# shield_confortimetro_bia_v2.net
KiCad netlist of a schematic drawn in EAGLE
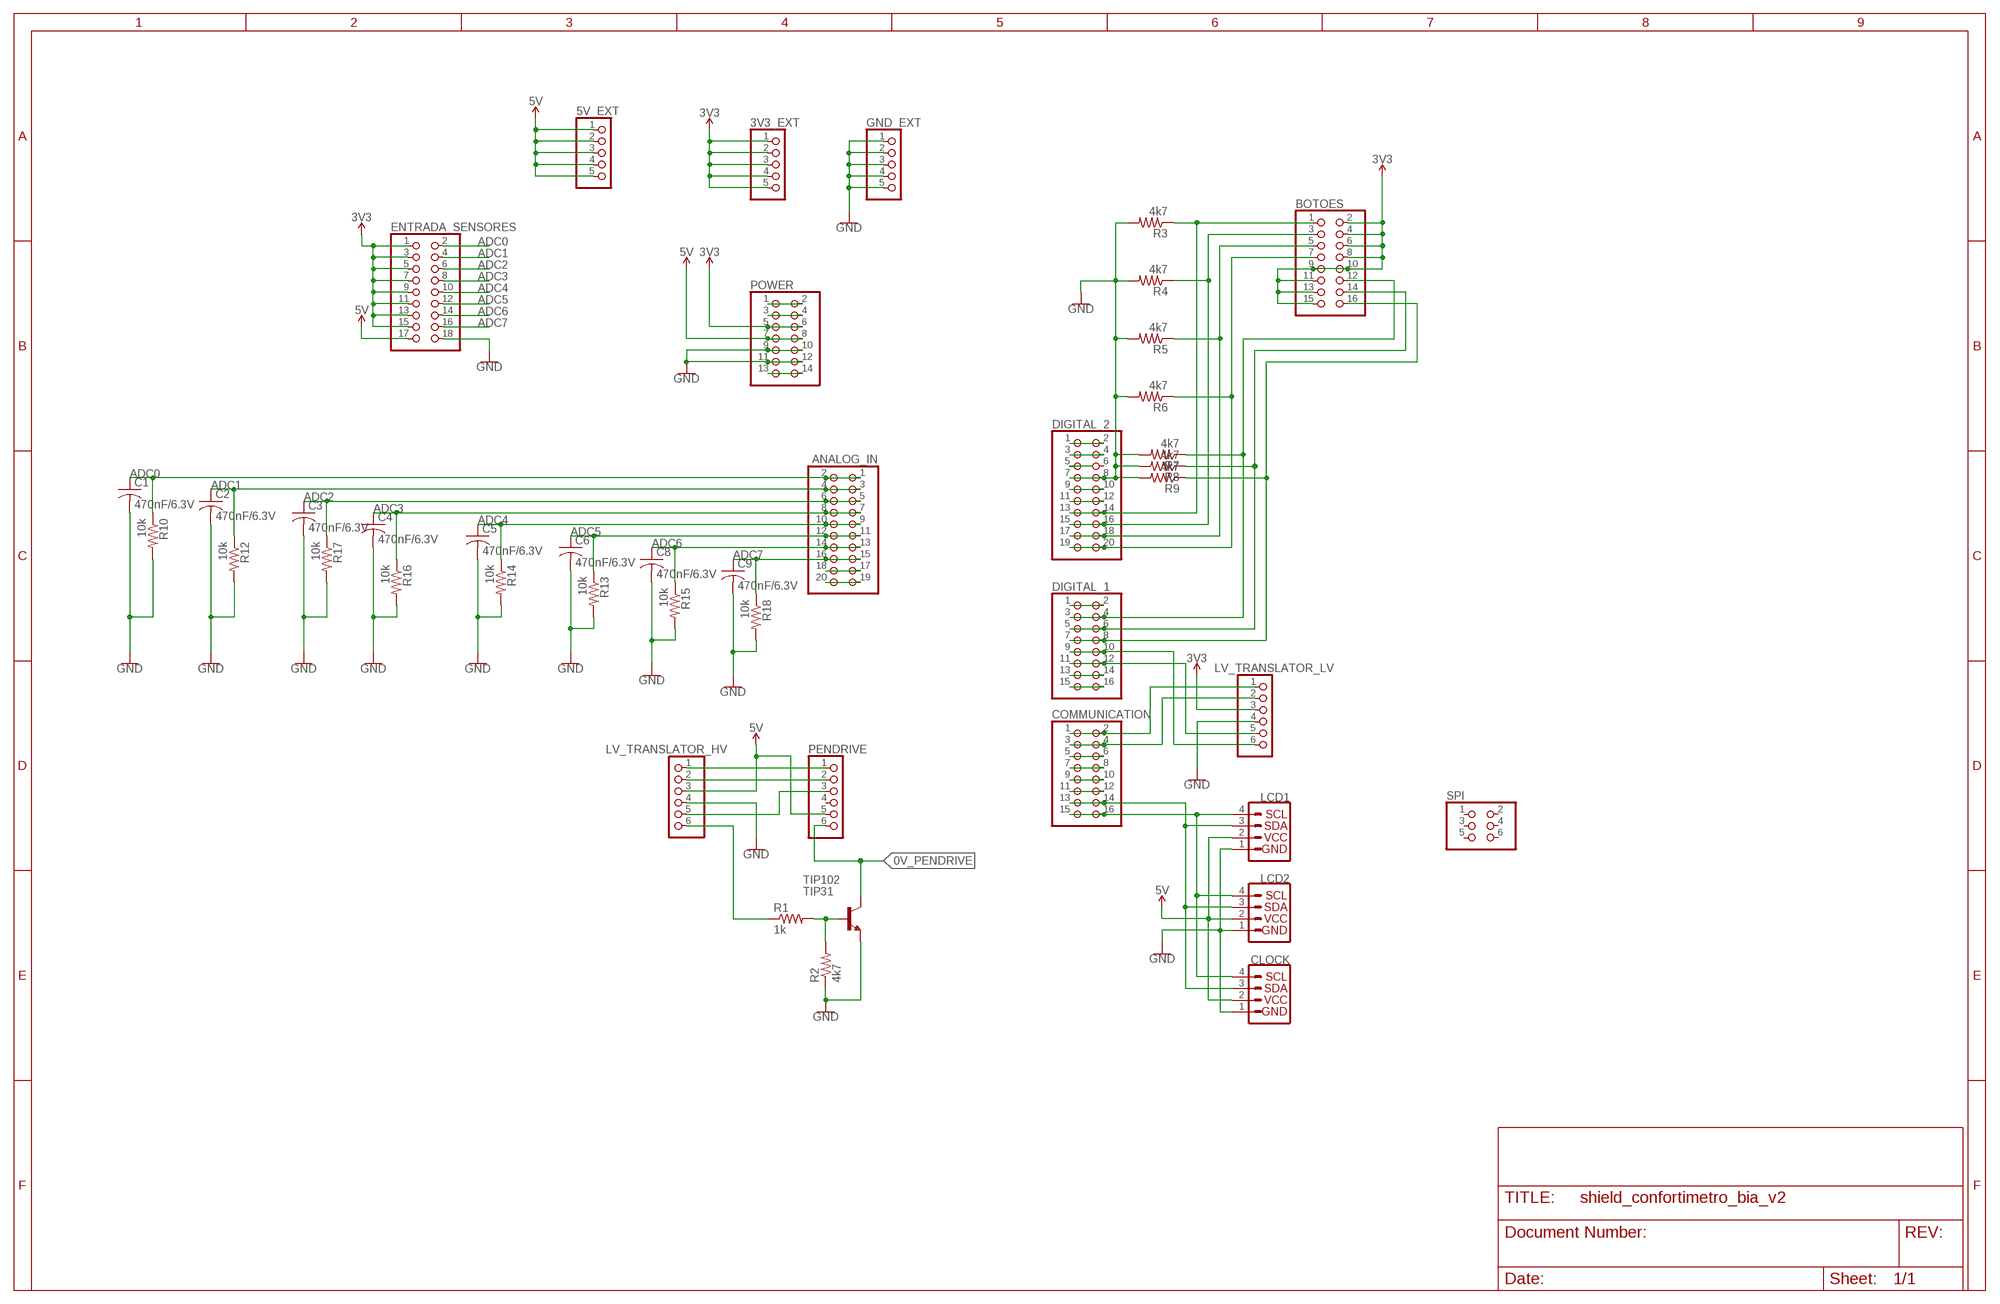
[diagram p0: schematic, sheet 1]

(export (version "E")
  (design (tool "Eeschema 10.0.6"))
  (components
    (comp (ref "3V3_EXT")
      (value "PINHD-1X5")
      (footprint "eagle-import:1X05")
      (libsource (lib "eagle-import") (part "PINHD-1X5"))
    )
    (comp (ref "5V_EXT")
      (value "PINHD-1X5")
      (footprint "eagle-import:1X05")
      (libsource (lib "eagle-import") (part "PINHD-1X5"))
    )
    (comp (ref "ANALOG_IN")
      (value "PINHD-2X10")
      (footprint "eagle-import:2X10")
      (libsource (lib "eagle-import") (part "PINHD-2X10"))
    )
    (comp (ref "BOTOES")
      (value "PINHD-2X8")
      (footprint "eagle-import:2X08")
      (libsource (lib "eagle-import") (part "PINHD-2X8"))
    )
    (comp (ref "C1")
      (value "470nF/6.3V")
      (footprint "eagle-import:C050-030X075")
      (libsource (lib "eagle-import") (part "C-US050-030X075"))
    )
    (comp (ref "C2")
      (value "470nF/6.3V")
      (footprint "eagle-import:C050-030X075")
      (libsource (lib "eagle-import") (part "C-US050-030X075"))
    )
    (comp (ref "C3")
      (value "470nF/6.3V")
      (footprint "eagle-import:C050-030X075")
      (libsource (lib "eagle-import") (part "C-US050-030X075"))
    )
    (comp (ref "C4")
      (value "470nF/6.3V")
      (footprint "eagle-import:C050-030X075")
      (libsource (lib "eagle-import") (part "C-US050-030X075"))
    )
    (comp (ref "C5")
      (value "470nF/6.3V")
      (footprint "eagle-import:C050-030X075")
      (libsource (lib "eagle-import") (part "C-US050-030X075"))
    )
    (comp (ref "C6")
      (value "470nF/6.3V")
      (footprint "eagle-import:C050-030X075")
      (libsource (lib "eagle-import") (part "C-US050-030X075"))
    )
    (comp (ref "C8")
      (value "470nF/6.3V")
      (footprint "eagle-import:C050-030X075")
      (libsource (lib "eagle-import") (part "C-US050-030X075"))
    )
    (comp (ref "C9")
      (value "470nF/6.3V")
      (footprint "eagle-import:C050-030X075")
      (libsource (lib "eagle-import") (part "C-US050-030X075"))
    )
    (comp (ref "CLOCK")
      (value "I2C_STANDARD")
      (footprint "eagle-import:1X04")
      (libsource (lib "eagle-import") (part "I2C_STANDARD"))
    )
    (comp (ref "COMMUNICATION")
      (value "PINHD-2X8")
      (footprint "eagle-import:2X08")
      (libsource (lib "eagle-import") (part "PINHD-2X8"))
    )
    (comp (ref "DIGITAL_1")
      (value "PINHD-2X8")
      (footprint "eagle-import:2X08")
      (libsource (lib "eagle-import") (part "PINHD-2X8"))
    )
    (comp (ref "DIGITAL_2")
      (value "PINHD-2X10")
      (footprint "eagle-import:2X10")
      (libsource (lib "eagle-import") (part "pinhead_PINHD-2X10"))
    )
    (comp (ref "ENTRADA_SENSORES")
      (value "PINHD-2X9")
      (footprint "eagle-import:2X09")
      (libsource (lib "eagle-import") (part "PINHD-2X9"))
    )
    (comp (ref "GND_EXT")
      (value "PINHD-1X5")
      (footprint "eagle-import:1X05")
      (libsource (lib "eagle-import") (part "PINHD-1X5"))
    )
    (comp (ref "LCD1")
      (value "I2C_STANDARD")
      (footprint "eagle-import:1X04")
      (libsource (lib "eagle-import") (part "I2C_STANDARD"))
    )
    (comp (ref "LCD2")
      (value "I2C_STANDARD")
      (footprint "eagle-import:1X04")
      (libsource (lib "eagle-import") (part "I2C_STANDARD"))
    )
    (comp (ref "LV_TRANSLATOR_HV")
      (value "PINHD-1X6")
      (footprint "eagle-import:1X06")
      (libsource (lib "eagle-import") (part "PINHD-1X6"))
    )
    (comp (ref "LV_TRANSLATOR_LV")
      (value "PINHD-1X6")
      (footprint "eagle-import:1X06")
      (libsource (lib "eagle-import") (part "PINHD-1X6"))
    )
    (comp (ref "PENDRIVE")
      (value "PINHD-1X6")
      (footprint "eagle-import:1X06")
      (libsource (lib "eagle-import") (part "PINHD-1X6"))
    )
    (comp (ref "POWER")
      (value "PINHD-2X7")
      (footprint "eagle-import:2X07")
      (libsource (lib "eagle-import") (part "PINHD-2X7"))
    )
    (comp (ref "R1")
      (value "1k")
      (footprint "eagle-import:0309_12")
      (libsource (lib "eagle-import") (part "R-US_0309/12"))
    )
    (comp (ref "R2")
      (value "4k7")
      (footprint "eagle-import:0309_12")
      (libsource (lib "eagle-import") (part "R-US_0309/12"))
    )
    (comp (ref "R3")
      (value "4k7")
      (footprint "eagle-import:0309_12")
      (libsource (lib "eagle-import") (part "R-US_0309/12"))
    )
    (comp (ref "R4")
      (value "4k7")
      (footprint "eagle-import:0309_12")
      (libsource (lib "eagle-import") (part "R-US_0309/12"))
    )
    (comp (ref "R5")
      (value "4k7")
      (footprint "eagle-import:0309_12")
      (libsource (lib "eagle-import") (part "R-US_0309/12"))
    )
    (comp (ref "R6")
      (value "4k7")
      (footprint "eagle-import:0309_12")
      (libsource (lib "eagle-import") (part "R-US_0309/12"))
    )
    (comp (ref "R7")
      (value "4k7")
      (footprint "eagle-import:0309_12")
      (libsource (lib "eagle-import") (part "R-US_0309/12"))
    )
    (comp (ref "R8")
      (value "4k7")
      (footprint "eagle-import:0309_12")
      (libsource (lib "eagle-import") (part "R-US_0309/12"))
    )
    (comp (ref "R9")
      (value "4k7")
      (footprint "eagle-import:0309_12")
      (libsource (lib "eagle-import") (part "R-US_0309/12"))
    )
    (comp (ref "R10")
      (value "10k")
      (footprint "eagle-import:0309_12")
      (libsource (lib "eagle-import") (part "R-US_0309/12"))
    )
    (comp (ref "R12")
      (value "10k")
      (footprint "eagle-import:0309_12")
      (libsource (lib "eagle-import") (part "R-US_0309/12"))
    )
    (comp (ref "R13")
      (value "10k")
      (footprint "eagle-import:0309_12")
      (libsource (lib "eagle-import") (part "R-US_0309/12"))
    )
    (comp (ref "R14")
      (value "10k")
      (footprint "eagle-import:0309_12")
      (libsource (lib "eagle-import") (part "R-US_0309/12"))
    )
    (comp (ref "R15")
      (value "10k")
      (footprint "eagle-import:0309_12")
      (libsource (lib "eagle-import") (part "R-US_0309/12"))
    )
    (comp (ref "R16")
      (value "10k")
      (footprint "eagle-import:0309_12")
      (libsource (lib "eagle-import") (part "R-US_0309/12"))
    )
    (comp (ref "R17")
      (value "10k")
      (footprint "eagle-import:0309_12")
      (libsource (lib "eagle-import") (part "R-US_0309/12"))
    )
    (comp (ref "R18")
      (value "10k")
      (footprint "eagle-import:0309_12")
      (libsource (lib "eagle-import") (part "R-US_0309/12"))
    )
    (comp (ref "SPI")
      (value "PINHD-2X3")
      (footprint "eagle-import:2X03")
      (libsource (lib "eagle-import") (part "PINHD-2X3"))
    )
    (comp (ref "TIP102")
      (value "TIP31")
      (footprint "eagle-import:TO220")
      (libsource (lib "eagle-import") (part "TIP31"))
    )
  )
  (nets
    (net (code "1") (name "/ADC0") (class "Default")
      (node (ref "ANALOG_IN") (pin "1") (pinfunction "1_1") (pintype "passive"))
      (node (ref "ANALOG_IN") (pin "2") (pinfunction "2_2") (pintype "passive"))
      (node (ref "C1") (pin "1") (pinfunction "1_1") (pintype "passive"))
      (node (ref "ENTRADA_SENSORES") (pin "2") (pinfunction "2_2") (pintype "passive"))
      (node (ref "R10") (pin "1") (pinfunction "1_1") (pintype "passive"))
    )
    (net (code "2") (name "/ADC1") (class "Default")
      (node (ref "ANALOG_IN") (pin "3") (pinfunction "3_3") (pintype "passive"))
      (node (ref "ANALOG_IN") (pin "4") (pinfunction "4_4") (pintype "passive"))
      (node (ref "C2") (pin "1") (pinfunction "1_1") (pintype "passive"))
      (node (ref "ENTRADA_SENSORES") (pin "4") (pinfunction "4_4") (pintype "passive"))
      (node (ref "R12") (pin "1") (pinfunction "1_1") (pintype "passive"))
    )
    (net (code "3") (name "/ADC2") (class "Default")
      (node (ref "ANALOG_IN") (pin "5") (pinfunction "5_5") (pintype "passive"))
      (node (ref "ANALOG_IN") (pin "6") (pinfunction "6_6") (pintype "passive"))
      (node (ref "C3") (pin "1") (pinfunction "1_1") (pintype "passive"))
      (node (ref "ENTRADA_SENSORES") (pin "6") (pinfunction "6_6") (pintype "passive"))
      (node (ref "R17") (pin "1") (pinfunction "1_1") (pintype "passive"))
    )
    (net (code "4") (name "/ADC3") (class "Default")
      (node (ref "ANALOG_IN") (pin "7") (pinfunction "7_7") (pintype "passive"))
      (node (ref "ANALOG_IN") (pin "8") (pinfunction "8_8") (pintype "passive"))
      (node (ref "C4") (pin "1") (pinfunction "1_1") (pintype "passive"))
      (node (ref "ENTRADA_SENSORES") (pin "8") (pinfunction "8_8") (pintype "passive"))
      (node (ref "R16") (pin "1") (pinfunction "1_1") (pintype "passive"))
    )
    (net (code "5") (name "/ADC4") (class "Default")
      (node (ref "ANALOG_IN") (pin "10") (pinfunction "10_10") (pintype "passive"))
      (node (ref "ANALOG_IN") (pin "9") (pinfunction "9_9") (pintype "passive"))
      (node (ref "C5") (pin "1") (pinfunction "1_1") (pintype "passive"))
      (node (ref "ENTRADA_SENSORES") (pin "10") (pinfunction "10_10") (pintype "passive"))
      (node (ref "R14") (pin "1") (pinfunction "1_1") (pintype "passive"))
    )
    (net (code "6") (name "/ADC5") (class "Default")
      (node (ref "ANALOG_IN") (pin "11") (pinfunction "11_11") (pintype "passive"))
      (node (ref "ANALOG_IN") (pin "12") (pinfunction "12_12") (pintype "passive"))
      (node (ref "C6") (pin "1") (pinfunction "1_1") (pintype "passive"))
      (node (ref "ENTRADA_SENSORES") (pin "12") (pinfunction "12_12") (pintype "passive"))
      (node (ref "R13") (pin "1") (pinfunction "1_1") (pintype "passive"))
    )
    (net (code "7") (name "/ADC6") (class "Default")
      (node (ref "ANALOG_IN") (pin "13") (pinfunction "13_13") (pintype "passive"))
      (node (ref "ANALOG_IN") (pin "14") (pinfunction "14_14") (pintype "passive"))
      (node (ref "C8") (pin "1") (pinfunction "1_1") (pintype "passive"))
      (node (ref "ENTRADA_SENSORES") (pin "14") (pinfunction "14_14") (pintype "passive"))
      (node (ref "R15") (pin "1") (pinfunction "1_1") (pintype "passive"))
    )
    (net (code "8") (name "/ADC7") (class "Default")
      (node (ref "ANALOG_IN") (pin "15") (pinfunction "15_15") (pintype "passive"))
      (node (ref "ANALOG_IN") (pin "16") (pinfunction "16_16") (pintype "passive"))
      (node (ref "C9") (pin "1") (pinfunction "1_1") (pintype "passive"))
      (node (ref "ENTRADA_SENSORES") (pin "16") (pinfunction "16_16") (pintype "passive"))
      (node (ref "R18") (pin "1") (pinfunction "1_1") (pintype "passive"))
    )
    (net (code "9") (name "0V_PENDRIVE") (class "Default")
      (node (ref "PENDRIVE") (pin "6") (pinfunction "6_6") (pintype "passive"))
      (node (ref "TIP102") (pin "2") (pinfunction "C_2") (pintype "passive"))
    )
    (net (code "10") (name "3V3") (class "Default")
      (node (ref "3V3_EXT") (pin "1") (pinfunction "1_1") (pintype "passive"))
      (node (ref "3V3_EXT") (pin "2") (pinfunction "2_2") (pintype "passive"))
      (node (ref "3V3_EXT") (pin "3") (pinfunction "3_3") (pintype "passive"))
      (node (ref "3V3_EXT") (pin "4") (pinfunction "4_4") (pintype "passive"))
      (node (ref "3V3_EXT") (pin "5") (pinfunction "5_5") (pintype "passive"))
      (node (ref "BOTOES") (pin "10") (pinfunction "10_10") (pintype "passive"))
      (node (ref "BOTOES") (pin "11") (pinfunction "11_11") (pintype "passive"))
      (node (ref "BOTOES") (pin "13") (pinfunction "13_13") (pintype "passive"))
      (node (ref "BOTOES") (pin "15") (pinfunction "15_15") (pintype "passive"))
      (node (ref "BOTOES") (pin "2") (pinfunction "2_2") (pintype "passive"))
      (node (ref "BOTOES") (pin "4") (pinfunction "4_4") (pintype "passive"))
      (node (ref "BOTOES") (pin "6") (pinfunction "6_6") (pintype "passive"))
      (node (ref "BOTOES") (pin "8") (pinfunction "8_8") (pintype "passive"))
      (node (ref "BOTOES") (pin "9") (pinfunction "9_9") (pintype "passive"))
      (node (ref "ENTRADA_SENSORES") (pin "1") (pinfunction "1_1") (pintype "passive"))
      (node (ref "ENTRADA_SENSORES") (pin "11") (pinfunction "11_11") (pintype "passive"))
      (node (ref "ENTRADA_SENSORES") (pin "13") (pinfunction "13_13") (pintype "passive"))
      (node (ref "ENTRADA_SENSORES") (pin "15") (pinfunction "15_15") (pintype "passive"))
      (node (ref "ENTRADA_SENSORES") (pin "3") (pinfunction "3_3") (pintype "passive"))
      (node (ref "ENTRADA_SENSORES") (pin "5") (pinfunction "5_5") (pintype "passive"))
      (node (ref "ENTRADA_SENSORES") (pin "7") (pinfunction "7_7") (pintype "passive"))
      (node (ref "ENTRADA_SENSORES") (pin "9") (pinfunction "9_9") (pintype "passive"))
      (node (ref "LV_TRANSLATOR_LV") (pin "3") (pinfunction "3_3") (pintype "passive"))
      (node (ref "POWER") (pin "5") (pinfunction "5_5") (pintype "passive"))
      (node (ref "POWER") (pin "6") (pinfunction "6_6") (pintype "passive"))
    )
    (net (code "11") (name "5V") (class "Default")
      (node (ref "5V_EXT") (pin "1") (pinfunction "1_1") (pintype "passive"))
      (node (ref "5V_EXT") (pin "2") (pinfunction "2_2") (pintype "passive"))
      (node (ref "5V_EXT") (pin "3") (pinfunction "3_3") (pintype "passive"))
      (node (ref "5V_EXT") (pin "4") (pinfunction "4_4") (pintype "passive"))
      (node (ref "5V_EXT") (pin "5") (pinfunction "5_5") (pintype "passive"))
      (node (ref "CLOCK") (pin "2") (pinfunction "2_2") (pintype "power_in"))
      (node (ref "ENTRADA_SENSORES") (pin "17") (pinfunction "17_17") (pintype "passive"))
      (node (ref "LCD1") (pin "2") (pinfunction "2_2") (pintype "power_in"))
      (node (ref "LCD2") (pin "2") (pinfunction "2_2") (pintype "power_in"))
      (node (ref "LV_TRANSLATOR_HV") (pin "3") (pinfunction "3_3") (pintype "passive"))
      (node (ref "PENDRIVE") (pin "5") (pinfunction "5_5") (pintype "passive"))
      (node (ref "POWER") (pin "7") (pinfunction "7_7") (pintype "passive"))
      (node (ref "POWER") (pin "8") (pinfunction "8_8") (pintype "passive"))
    )
    (net (code "12") (name "GND") (class "Default")
      (node (ref "C1") (pin "2") (pinfunction "2_2") (pintype "passive"))
      (node (ref "C2") (pin "2") (pinfunction "2_2") (pintype "passive"))
      (node (ref "C3") (pin "2") (pinfunction "2_2") (pintype "passive"))
      (node (ref "C4") (pin "2") (pinfunction "2_2") (pintype "passive"))
      (node (ref "C5") (pin "2") (pinfunction "2_2") (pintype "passive"))
      (node (ref "C6") (pin "2") (pinfunction "2_2") (pintype "passive"))
      (node (ref "C8") (pin "2") (pinfunction "2_2") (pintype "passive"))
      (node (ref "C9") (pin "2") (pinfunction "2_2") (pintype "passive"))
      (node (ref "CLOCK") (pin "1") (pinfunction "1_1") (pintype "power_in"))
      (node (ref "DIGITAL_2") (pin "7") (pinfunction "7_7") (pintype "passive"))
      (node (ref "DIGITAL_2") (pin "8") (pinfunction "8_8") (pintype "passive"))
      (node (ref "ENTRADA_SENSORES") (pin "18") (pinfunction "18_18") (pintype "passive"))
      (node (ref "GND_EXT") (pin "1") (pinfunction "1_1") (pintype "passive"))
      (node (ref "GND_EXT") (pin "2") (pinfunction "2_2") (pintype "passive"))
      (node (ref "GND_EXT") (pin "3") (pinfunction "3_3") (pintype "passive"))
      (node (ref "GND_EXT") (pin "4") (pinfunction "4_4") (pintype "passive"))
      (node (ref "GND_EXT") (pin "5") (pinfunction "5_5") (pintype "passive"))
      (node (ref "LCD1") (pin "1") (pinfunction "1_1") (pintype "power_in"))
      (node (ref "LCD2") (pin "1") (pinfunction "1_1") (pintype "power_in"))
      (node (ref "LV_TRANSLATOR_HV") (pin "4") (pinfunction "4_4") (pintype "passive"))
      (node (ref "LV_TRANSLATOR_LV") (pin "4") (pinfunction "4_4") (pintype "passive"))
      (node (ref "POWER") (pin "10") (pinfunction "10_10") (pintype "passive"))
      (node (ref "POWER") (pin "11") (pinfunction "11_11") (pintype "passive"))
      (node (ref "POWER") (pin "12") (pinfunction "12_12") (pintype "passive"))
      (node (ref "POWER") (pin "9") (pinfunction "9_9") (pintype "passive"))
      (node (ref "R10") (pin "2") (pinfunction "2_2") (pintype "passive"))
      (node (ref "R12") (pin "2") (pinfunction "2_2") (pintype "passive"))
      (node (ref "R13") (pin "2") (pinfunction "2_2") (pintype "passive"))
      (node (ref "R14") (pin "2") (pinfunction "2_2") (pintype "passive"))
      (node (ref "R15") (pin "2") (pinfunction "2_2") (pintype "passive"))
      (node (ref "R16") (pin "2") (pinfunction "2_2") (pintype "passive"))
      (node (ref "R17") (pin "2") (pinfunction "2_2") (pintype "passive"))
      (node (ref "R18") (pin "2") (pinfunction "2_2") (pintype "passive"))
      (node (ref "R2") (pin "1") (pinfunction "1_1") (pintype "passive"))
      (node (ref "R3") (pin "2") (pinfunction "2_2") (pintype "passive"))
      (node (ref "R4") (pin "2") (pinfunction "2_2") (pintype "passive"))
      (node (ref "R5") (pin "2") (pinfunction "2_2") (pintype "passive"))
      (node (ref "R6") (pin "2") (pinfunction "2_2") (pintype "passive"))
      (node (ref "R7") (pin "2") (pinfunction "2_2") (pintype "passive"))
      (node (ref "R8") (pin "2") (pinfunction "2_2") (pintype "passive"))
      (node (ref "R9") (pin "2") (pinfunction "2_2") (pintype "passive"))
      (node (ref "TIP102") (pin "3") (pinfunction "E_3") (pintype "passive"))
    )
    (net (code "13") (name "Net-(ANALOG_IN-Pad17)") (class "Default")
      (node (ref "ANALOG_IN") (pin "17") (pinfunction "17_17") (pintype "passive"))
      (node (ref "ANALOG_IN") (pin "18") (pinfunction "18_18") (pintype "passive"))
    )
    (net (code "14") (name "Net-(ANALOG_IN-Pad19)") (class "Default")
      (node (ref "ANALOG_IN") (pin "19") (pinfunction "19_19") (pintype "passive"))
      (node (ref "ANALOG_IN") (pin "20") (pinfunction "20_20") (pintype "passive"))
    )
    (net (code "15") (name "Net-(BOTOES-Pad1)") (class "Default")
      (node (ref "BOTOES") (pin "1") (pinfunction "1_1") (pintype "passive"))
      (node (ref "DIGITAL_2") (pin "13") (pinfunction "13_13") (pintype "passive"))
      (node (ref "DIGITAL_2") (pin "14") (pinfunction "14_14") (pintype "passive"))
      (node (ref "R3") (pin "1") (pinfunction "1_1") (pintype "passive"))
    )
    (net (code "16") (name "Net-(BOTOES-Pad3)") (class "Default")
      (node (ref "BOTOES") (pin "3") (pinfunction "3_3") (pintype "passive"))
      (node (ref "DIGITAL_2") (pin "15") (pinfunction "15_15") (pintype "passive"))
      (node (ref "DIGITAL_2") (pin "16") (pinfunction "16_16") (pintype "passive"))
      (node (ref "R4") (pin "1") (pinfunction "1_1") (pintype "passive"))
    )
    (net (code "17") (name "Net-(BOTOES-Pad5)") (class "Default")
      (node (ref "BOTOES") (pin "5") (pinfunction "5_5") (pintype "passive"))
      (node (ref "DIGITAL_2") (pin "17") (pinfunction "17_17") (pintype "passive"))
      (node (ref "DIGITAL_2") (pin "18") (pinfunction "18_18") (pintype "passive"))
      (node (ref "R5") (pin "1") (pinfunction "1_1") (pintype "passive"))
    )
    (net (code "18") (name "Net-(BOTOES-Pad7)") (class "Default")
      (node (ref "BOTOES") (pin "7") (pinfunction "7_7") (pintype "passive"))
      (node (ref "DIGITAL_2") (pin "19") (pinfunction "19_19") (pintype "passive"))
      (node (ref "DIGITAL_2") (pin "20") (pinfunction "20_20") (pintype "passive"))
      (node (ref "R6") (pin "1") (pinfunction "1_1") (pintype "passive"))
    )
    (net (code "19") (name "Net-(BOTOES-Pad12)") (class "Default")
      (node (ref "BOTOES") (pin "12") (pinfunction "12_12") (pintype "passive"))
      (node (ref "DIGITAL_1") (pin "3") (pinfunction "3_3") (pintype "passive"))
      (node (ref "DIGITAL_1") (pin "4") (pinfunction "4_4") (pintype "passive"))
      (node (ref "R7") (pin "1") (pinfunction "1_1") (pintype "passive"))
    )
    (net (code "20") (name "Net-(BOTOES-Pad14)") (class "Default")
      (node (ref "BOTOES") (pin "14") (pinfunction "14_14") (pintype "passive"))
      (node (ref "DIGITAL_1") (pin "5") (pinfunction "5_5") (pintype "passive"))
      (node (ref "DIGITAL_1") (pin "6") (pinfunction "6_6") (pintype "passive"))
      (node (ref "R8") (pin "1") (pinfunction "1_1") (pintype "passive"))
    )
    (net (code "21") (name "Net-(BOTOES-Pad16)") (class "Default")
      (node (ref "BOTOES") (pin "16") (pinfunction "16_16") (pintype "passive"))
      (node (ref "DIGITAL_1") (pin "7") (pinfunction "7_7") (pintype "passive"))
      (node (ref "DIGITAL_1") (pin "8") (pinfunction "8_8") (pintype "passive"))
      (node (ref "R9") (pin "1") (pinfunction "1_1") (pintype "passive"))
    )
    (net (code "22") (name "Net-(CLOCK-Pad3)") (class "Default")
      (node (ref "CLOCK") (pin "3") (pinfunction "3_3") (pintype "passive"))
      (node (ref "COMMUNICATION") (pin "13") (pinfunction "13_13") (pintype "passive"))
      (node (ref "COMMUNICATION") (pin "14") (pinfunction "14_14") (pintype "passive"))
      (node (ref "LCD1") (pin "3") (pinfunction "3_3") (pintype "passive"))
      (node (ref "LCD2") (pin "3") (pinfunction "3_3") (pintype "passive"))
    )
    (net (code "23") (name "Net-(CLOCK-Pad4)") (class "Default")
      (node (ref "CLOCK") (pin "4") (pinfunction "4_4") (pintype "passive"))
      (node (ref "COMMUNICATION") (pin "15") (pinfunction "15_15") (pintype "passive"))
      (node (ref "COMMUNICATION") (pin "16") (pinfunction "16_16") (pintype "passive"))
      (node (ref "LCD1") (pin "4") (pinfunction "4_4") (pintype "passive"))
      (node (ref "LCD2") (pin "4") (pinfunction "4_4") (pintype "passive"))
    )
    (net (code "24") (name "Net-(COMMUNICATION-Pad1)") (class "Default")
      (node (ref "COMMUNICATION") (pin "1") (pinfunction "1_1") (pintype "passive"))
      (node (ref "COMMUNICATION") (pin "2") (pinfunction "2_2") (pintype "passive"))
      (node (ref "LV_TRANSLATOR_LV") (pin "1") (pinfunction "1_1") (pintype "passive"))
    )
    (net (code "25") (name "Net-(COMMUNICATION-Pad3)") (class "Default")
      (node (ref "COMMUNICATION") (pin "3") (pinfunction "3_3") (pintype "passive"))
      (node (ref "COMMUNICATION") (pin "4") (pinfunction "4_4") (pintype "passive"))
      (node (ref "LV_TRANSLATOR_LV") (pin "2") (pinfunction "2_2") (pintype "passive"))
    )
    (net (code "26") (name "Net-(COMMUNICATION-Pad5)") (class "Default")
      (node (ref "COMMUNICATION") (pin "5") (pinfunction "5_5") (pintype "passive"))
      (node (ref "COMMUNICATION") (pin "6") (pinfunction "6_6") (pintype "passive"))
    )
    (net (code "27") (name "Net-(COMMUNICATION-Pad7)") (class "Default")
      (node (ref "COMMUNICATION") (pin "7") (pinfunction "7_7") (pintype "passive"))
      (node (ref "COMMUNICATION") (pin "8") (pinfunction "8_8") (pintype "passive"))
    )
    (net (code "28") (name "Net-(COMMUNICATION-Pad10)") (class "Default")
      (node (ref "COMMUNICATION") (pin "10") (pinfunction "10_10") (pintype "passive"))
      (node (ref "COMMUNICATION") (pin "9") (pinfunction "9_9") (pintype "passive"))
    )
    (net (code "29") (name "Net-(COMMUNICATION-Pad11)") (class "Default")
      (node (ref "COMMUNICATION") (pin "11") (pinfunction "11_11") (pintype "passive"))
      (node (ref "COMMUNICATION") (pin "12") (pinfunction "12_12") (pintype "passive"))
    )
    (net (code "30") (name "Net-(DIGITAL_1-Pad1)") (class "Default")
      (node (ref "DIGITAL_1") (pin "1") (pinfunction "1_1") (pintype "passive"))
      (node (ref "DIGITAL_1") (pin "2") (pinfunction "2_2") (pintype "passive"))
    )
    (net (code "31") (name "Net-(DIGITAL_1-Pad10)") (class "Default")
      (node (ref "DIGITAL_1") (pin "10") (pinfunction "10_10") (pintype "passive"))
      (node (ref "DIGITAL_1") (pin "9") (pinfunction "9_9") (pintype "passive"))
      (node (ref "LV_TRANSLATOR_LV") (pin "6") (pinfunction "6_6") (pintype "passive"))
    )
    (net (code "32") (name "Net-(DIGITAL_1-Pad11)") (class "Default")
      (node (ref "DIGITAL_1") (pin "11") (pinfunction "11_11") (pintype "passive"))
      (node (ref "DIGITAL_1") (pin "12") (pinfunction "12_12") (pintype "passive"))
      (node (ref "LV_TRANSLATOR_LV") (pin "5") (pinfunction "5_5") (pintype "passive"))
    )
    (net (code "33") (name "Net-(DIGITAL_1-Pad13)") (class "Default")
      (node (ref "DIGITAL_1") (pin "13") (pinfunction "13_13") (pintype "passive"))
      (node (ref "DIGITAL_1") (pin "14") (pinfunction "14_14") (pintype "passive"))
    )
    (net (code "34") (name "Net-(DIGITAL_1-Pad15)") (class "Default")
      (node (ref "DIGITAL_1") (pin "15") (pinfunction "15_15") (pintype "passive"))
      (node (ref "DIGITAL_1") (pin "16") (pinfunction "16_16") (pintype "passive"))
    )
    (net (code "35") (name "Net-(DIGITAL_2-Pad1)") (class "Default")
      (node (ref "DIGITAL_2") (pin "1") (pinfunction "1_1") (pintype "passive"))
      (node (ref "DIGITAL_2") (pin "2") (pinfunction "2_2") (pintype "passive"))
    )
    (net (code "36") (name "Net-(DIGITAL_2-Pad3)") (class "Default")
      (node (ref "DIGITAL_2") (pin "3") (pinfunction "3_3") (pintype "passive"))
      (node (ref "DIGITAL_2") (pin "4") (pinfunction "4_4") (pintype "passive"))
    )
    (net (code "37") (name "Net-(DIGITAL_2-Pad10)") (class "Default")
      (node (ref "DIGITAL_2") (pin "10") (pinfunction "10_10") (pintype "passive"))
      (node (ref "DIGITAL_2") (pin "9") (pinfunction "9_9") (pintype "passive"))
    )
    (net (code "38") (name "Net-(DIGITAL_2-Pad11)") (class "Default")
      (node (ref "DIGITAL_2") (pin "11") (pinfunction "11_11") (pintype "passive"))
      (node (ref "DIGITAL_2") (pin "12") (pinfunction "12_12") (pintype "passive"))
    )
    (net (code "39") (name "Net-(LV_TRANSLATOR_HV-Pad1)") (class "Default")
      (node (ref "LV_TRANSLATOR_HV") (pin "1") (pinfunction "1_1") (pintype "passive"))
      (node (ref "PENDRIVE") (pin "1") (pinfunction "1_1") (pintype "passive"))
    )
    (net (code "40") (name "Net-(LV_TRANSLATOR_HV-Pad2)") (class "Default")
      (node (ref "LV_TRANSLATOR_HV") (pin "2") (pinfunction "2_2") (pintype "passive"))
      (node (ref "PENDRIVE") (pin "2") (pinfunction "2_2") (pintype "passive"))
    )
    (net (code "41") (name "Net-(LV_TRANSLATOR_HV-Pad5)") (class "Default")
      (node (ref "LV_TRANSLATOR_HV") (pin "5") (pinfunction "5_5") (pintype "passive"))
      (node (ref "PENDRIVE") (pin "3") (pinfunction "3_3") (pintype "passive"))
    )
    (net (code "42") (name "Net-(LV_TRANSLATOR_HV-Pad6)") (class "Default")
      (node (ref "LV_TRANSLATOR_HV") (pin "6") (pinfunction "6_6") (pintype "passive"))
      (node (ref "R1") (pin "1") (pinfunction "1_1") (pintype "passive"))
    )
    (net (code "43") (name "Net-(POWER-Pad1)") (class "Default")
      (node (ref "POWER") (pin "1") (pinfunction "1_1") (pintype "passive"))
      (node (ref "POWER") (pin "2") (pinfunction "2_2") (pintype "passive"))
    )
    (net (code "44") (name "Net-(POWER-Pad3)") (class "Default")
      (node (ref "POWER") (pin "3") (pinfunction "3_3") (pintype "passive"))
      (node (ref "POWER") (pin "4") (pinfunction "4_4") (pintype "passive"))
    )
    (net (code "45") (name "Net-(POWER-Pad13)") (class "Default")
      (node (ref "POWER") (pin "13") (pinfunction "13_13") (pintype "passive"))
      (node (ref "POWER") (pin "14") (pinfunction "14_14") (pintype "passive"))
    )
    (net (code "46") (name "Net-(TIP102-B)") (class "Default")
      (node (ref "R1") (pin "2") (pinfunction "2_2") (pintype "passive"))
      (node (ref "R2") (pin "2") (pinfunction "2_2") (pintype "passive"))
      (node (ref "TIP102") (pin "1") (pinfunction "B_1") (pintype "passive"))
    )
    (net (code "47") (name "unconnected-(DIGITAL_2-Pad5)") (class "Default")
      (node (ref "DIGITAL_2") (pin "5") (pinfunction "5_5") (pintype "passive"))
    )
    (net (code "48") (name "unconnected-(DIGITAL_2-Pad6)") (class "Default")
      (node (ref "DIGITAL_2") (pin "6") (pinfunction "6_6") (pintype "passive"))
    )
    (net (code "49") (name "unconnected-(PENDRIVE-Pad4)") (class "Default")
      (node (ref "PENDRIVE") (pin "4") (pinfunction "4_4") (pintype "passive"))
    )
    (net (code "50") (name "unconnected-(SPI-Pad1)") (class "Default")
      (node (ref "SPI") (pin "1") (pinfunction "1_1") (pintype "passive"))
    )
    (net (code "51") (name "unconnected-(SPI-Pad2)") (class "Default")
      (node (ref "SPI") (pin "2") (pinfunction "2_2") (pintype "passive"))
    )
    (net (code "52") (name "unconnected-(SPI-Pad3)") (class "Default")
      (node (ref "SPI") (pin "3") (pinfunction "3_3") (pintype "passive"))
    )
    (net (code "53") (name "unconnected-(SPI-Pad4)") (class "Default")
      (node (ref "SPI") (pin "4") (pinfunction "4_4") (pintype "passive"))
    )
    (net (code "54") (name "unconnected-(SPI-Pad5)") (class "Default")
      (node (ref "SPI") (pin "5") (pinfunction "5_5") (pintype "passive"))
    )
    (net (code "55") (name "unconnected-(SPI-Pad6)") (class "Default")
      (node (ref "SPI") (pin "6") (pinfunction "6_6") (pintype "passive"))
    )
  )
)
